# Power.net
KiCad netlist of a schematic drawn in Altium Designer
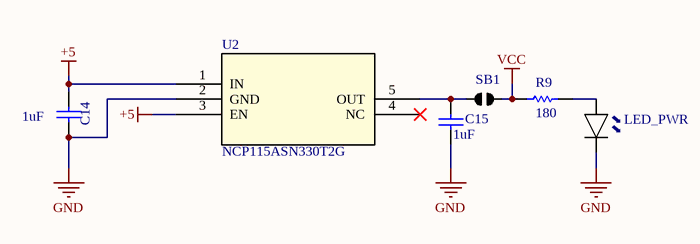
[diagram p0: Power.SchDoc]

(export (version "E")
  (design (tool "Eeschema 10.0.6"))
  (components
    (comp (ref "C14")
      (value "1uF")
      (footprint "J1-0603")
      (description "Capacitor")
      (fields (field (name "Comment") "C15849") (field (name "PUBLISHER") "Altium Limited"))
      (libsource (lib "Miscellaneous Devices") (part "Cap"))
    )
    (comp (ref "C15")
      (value "1uF")
      (footprint "J1-0603")
      (description "Capacitor")
      (fields (field (name "Comment") "C15849") (field (name "PUBLISHER") "Altium Limited"))
      (libsource (lib "Miscellaneous Devices") (part "Cap"))
    )
    (comp (ref "LED_PWR")
      (value "C2286")
      (footprint "SamacSys:LEDC1608X70N")
      (libsource (lib "Schlib1") (part "fucking led maat hoe moeilijk ist kutprogram"))
    )
    (comp (ref "R9")
      (value "180")
      (footprint "J1-0603")
      (description "C22828")
      (fields (field (name "PUBLISHER") "Altium Limited"))
      (libsource (lib "Miscellaneous Devices") (part "Res1"))
    )
    (comp (ref "SB1")
      (value "Solder Bridge")
      (footprint "Solder Bridge")
      (description "DNP")
      (libsource (lib "schematic") (part "Solder Bridge"))
    )
    (comp (ref "U2")
      (value "NCP115ASN330T2G")
      (footprint "SOT95P275X120-5N")
      (description "C603505")
      (fields (field (name "COPYRIGHT") "Copyright (C) 2023 Ultra Librarian. All rights reserved."))
      (libsource (lib "NCP115ASN330T2G") (part "NCP115ASN330T2G"))
    )
  )
  (nets
    (net (code "1") (name "+5") (class "Default")
      (node (ref "C14") (pin "2") (pinfunction "2_2") (pintype "passive"))
      (node (ref "U2") (pin "1") (pinfunction "IN_1") (pintype "passive"))
      (node (ref "U2") (pin "3") (pinfunction "EN_3") (pintype "passive"))
    )
    (net (code "2") (name "GND") (class "Default")
      (node (ref "C14") (pin "1") (pinfunction "1_1") (pintype "passive"))
      (node (ref "C15") (pin "1") (pinfunction "1_1") (pintype "passive"))
      (node (ref "LED_PWR") (pin "1") (pinfunction "1_1") (pintype "passive"))
      (node (ref "U2") (pin "2") (pinfunction "GND_2") (pintype "power_in"))
    )
    (net (code "3") (name "Net-(LED_PWR-Pad2)") (class "Default")
      (node (ref "LED_PWR") (pin "2") (pinfunction "2_2") (pintype "passive"))
      (node (ref "R9") (pin "2") (pinfunction "2_2") (pintype "passive"))
    )
    (net (code "4") (name "Net-(U2-OUT)") (class "Default")
      (node (ref "C15") (pin "2") (pinfunction "2_2") (pintype "passive"))
      (node (ref "SB1") (pin "1") (pinfunction "3_1") (pintype "passive"))
      (node (ref "U2") (pin "5") (pinfunction "OUT_5") (pintype "passive"))
    )
    (net (code "5") (name "VCC") (class "Default")
      (node (ref "R9") (pin "1") (pinfunction "1_1") (pintype "passive"))
      (node (ref "SB1") (pin "2") (pinfunction "3_2") (pintype "passive"))
    )
    (net (code "6") (name "unconnected-(U2-NC-Pad4)") (class "Default")
      (node (ref "U2") (pin "4") (pinfunction "NC_4") (pintype "passive+no_connect"))
    )
  )
)
